# Cube.net
KiCad netlist of a schematic drawn in EAGLE
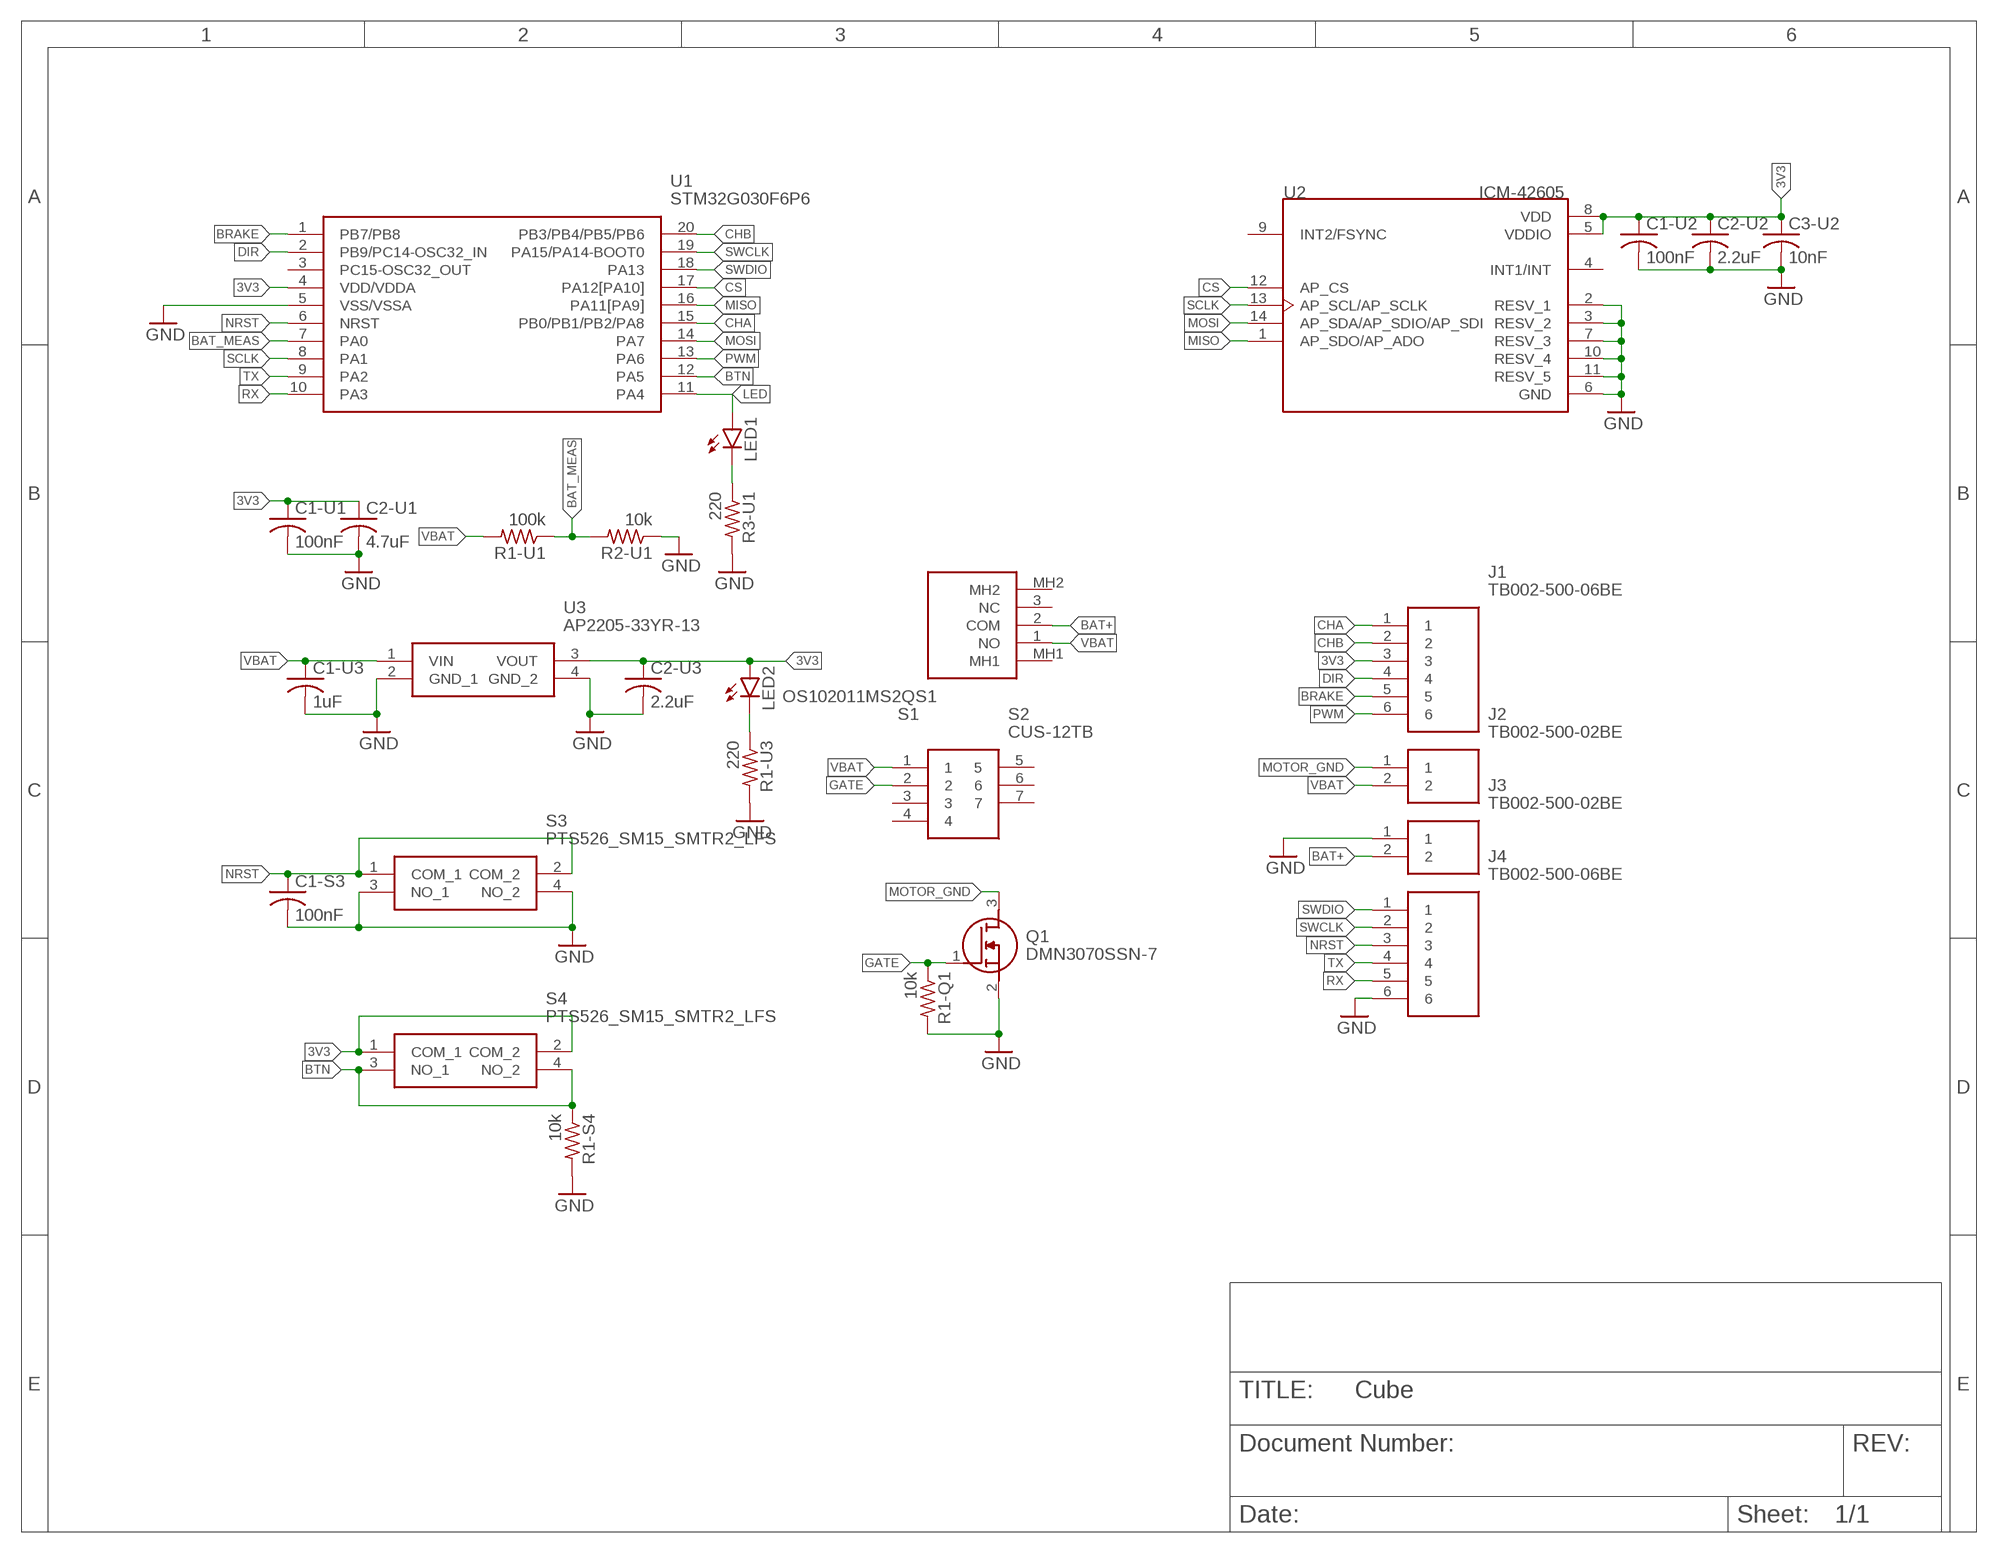
[diagram p0: schematic, sheet 1]

(export (version "E")
  (design (tool "Eeschema 10.0.6"))
  (components
    (comp (ref "C1-S3")
      (value "100nF")
      (footprint "eagle-import:C0805")
      (libsource (lib "eagle-import") (part "C-USC0805"))
    )
    (comp (ref "C1-U1")
      (value "100nF")
      (footprint "eagle-import:C0805")
      (libsource (lib "eagle-import") (part "C-USC0805"))
    )
    (comp (ref "C1-U2")
      (value "100nF")
      (footprint "eagle-import:C0805")
      (libsource (lib "eagle-import") (part "C-USC0805"))
    )
    (comp (ref "C1-U3")
      (value "1uF")
      (footprint "eagle-import:C0805")
      (libsource (lib "eagle-import") (part "C-USC0805"))
    )
    (comp (ref "C2-U1")
      (value "4.7uF")
      (footprint "eagle-import:C0805")
      (libsource (lib "eagle-import") (part "C-USC0805"))
    )
    (comp (ref "C2-U2")
      (value "2.2uF")
      (footprint "eagle-import:C0805")
      (libsource (lib "eagle-import") (part "C-USC0805"))
    )
    (comp (ref "C2-U3")
      (value "2.2uF")
      (footprint "eagle-import:C0805")
      (libsource (lib "eagle-import") (part "C-USC0805"))
    )
    (comp (ref "C3-U2")
      (value "10nF")
      (footprint "eagle-import:C0805")
      (libsource (lib "eagle-import") (part "C-USC0805"))
    )
    (comp (ref "J1")
      (value "TB002-500-06BE")
      (footprint "eagle-import:TB00250006BE")
      (fields (field (name "MOUSER_PART_NUMBER") "490-TB002-500-06BE"))
      (libsource (lib "eagle-import") (part "TB002-500-06BE"))
    )
    (comp (ref "J2")
      (value "TB002-500-02BE")
      (footprint "eagle-import:TB00250002BE")
      (fields (field (name "MOUSER_PART_NUMBER") "490-TB002-500-02BE"))
      (libsource (lib "eagle-import") (part "TB002-500-02BE"))
    )
    (comp (ref "J3")
      (value "TB002-500-02BE")
      (footprint "eagle-import:TB00250002BE")
      (fields (field (name "MOUSER_PART_NUMBER") "490-TB002-500-02BE"))
      (libsource (lib "eagle-import") (part "TB002-500-02BE"))
    )
    (comp (ref "J4")
      (value "TB002-500-06BE")
      (footprint "eagle-import:TB00250006BE")
      (fields (field (name "MOUSER_PART_NUMBER") "490-TB002-500-06BE"))
      (libsource (lib "eagle-import") (part "TB002-500-06BE"))
    )
    (comp (ref "LED1")
      (value "LEDCHIP-LED0805")
      (footprint "eagle-import:CHIP-LED0805")
      (libsource (lib "eagle-import") (part "LEDCHIP-LED0805"))
    )
    (comp (ref "LED2")
      (value "LEDCHIP-LED0805")
      (footprint "eagle-import:CHIP-LED0805")
      (libsource (lib "eagle-import") (part "LEDCHIP-LED0805"))
    )
    (comp (ref "Q1")
      (value "DMN3070SSN-7")
      (footprint "eagle-import:SOT95P285X140-3N")
      (fields (field (name "MOUSER_PART_NUMBER") "621-DMN3070SSN-7"))
      (libsource (lib "eagle-import") (part "DMN3070SSN-7"))
    )
    (comp (ref "R1-Q1")
      (value "10k")
      (footprint "eagle-import:R0805")
      (libsource (lib "eagle-import") (part "R-US_R0805"))
    )
    (comp (ref "R1-S4")
      (value "10k")
      (footprint "eagle-import:R0805")
      (libsource (lib "eagle-import") (part "R-US_R0805"))
    )
    (comp (ref "R1-U1")
      (value "100k")
      (footprint "eagle-import:R0805")
      (libsource (lib "eagle-import") (part "R-US_R0805"))
    )
    (comp (ref "R1-U3")
      (value "220")
      (footprint "eagle-import:R0805")
      (libsource (lib "eagle-import") (part "R-US_R0805"))
    )
    (comp (ref "R2-U1")
      (value "10k")
      (footprint "eagle-import:R0805")
      (libsource (lib "eagle-import") (part "R-US_R0805"))
    )
    (comp (ref "R3-U1")
      (value "220")
      (footprint "eagle-import:R0805")
      (libsource (lib "eagle-import") (part "R-US_R0805"))
    )
    (comp (ref "S1")
      (value "OS102011MS2QS1")
      (footprint "eagle-import:OS102011MS2QS1")
      (fields (field (name "MOUSER_PART_NUMBER") "611-OS102011MS2QS1"))
      (libsource (lib "eagle-import") (part "OS102011MS2QS1"))
    )
    (comp (ref "S2")
      (value "CUS-12TB")
      (footprint "eagle-import:CUS-12B")
      (libsource (lib "eagle-import") (part "CUS-12TB"))
    )
    (comp (ref "S3")
      (value "PTS526_SM15_SMTR2_LFS")
      (footprint "eagle-import:PTS526SM15SMTR2LFS")
      (fields
        (field (name "MANUFACTURER_PART_NUMBER") "PTS526 SM15 SMTR2 LFS")
        (field (name "MOUSER_PART_NUMBER") "611-PTS526SM15SMTR2L")
      )
      (libsource (lib "eagle-import") (part "PTS526_SM15_SMTR2_LFS"))
    )
    (comp (ref "S4")
      (value "PTS526_SM15_SMTR2_LFS")
      (footprint "eagle-import:PTS526SM15SMTR2LFS")
      (fields
        (field (name "MANUFACTURER_PART_NUMBER") "PTS526 SM15 SMTR2 LFS")
        (field (name "MOUSER_PART_NUMBER") "611-PTS526SM15SMTR2L")
      )
      (libsource (lib "eagle-import") (part "PTS526_SM15_SMTR2_LFS"))
    )
    (comp (ref "U1")
      (value "STM32G030F6P6")
      (footprint "eagle-import:SOP65P640X120-20N")
      (fields (field (name "MOUSER_PART_NUMBER") "511-STM32G030F6P6"))
      (libsource (lib "eagle-import") (part "STM32G030F6P6"))
    )
    (comp (ref "U2")
      (value "ICM-42605")
      (footprint "eagle-import:PQFN50P300X250X97-14N")
      (fields (field (name "MF") "TDK InvenSense"))
      (libsource (lib "eagle-import") (part "ICM-42605"))
    )
    (comp (ref "U3")
      (value "AP2205-33YR-13")
      (footprint "eagle-import:AP220533YR13")
      (fields (field (name "MOUSER_PART_NUMBER") "621-AP2205-33YR-13"))
      (libsource (lib "eagle-import") (part "AP2205-33YR-13"))
    )
  )
  (nets
    (net (code "1") (name "3V3") (class "Default")
      (node (ref "C1-U1") (pin "1") (pinfunction "1_1") (pintype "passive"))
      (node (ref "C1-U2") (pin "1") (pinfunction "1_1") (pintype "passive"))
      (node (ref "C2-U1") (pin "1") (pinfunction "1_1") (pintype "passive"))
      (node (ref "C2-U2") (pin "1") (pinfunction "1_1") (pintype "passive"))
      (node (ref "C2-U3") (pin "1") (pinfunction "1_1") (pintype "passive"))
      (node (ref "C3-U2") (pin "1") (pinfunction "1_1") (pintype "passive"))
      (node (ref "J1") (pin "3") (pinfunction "3_3") (pintype "bidirectional"))
      (node (ref "LED2") (pin "A") (pinfunction "A_A") (pintype "passive"))
      (node (ref "S4") (pin "1") (pinfunction "COM_1_1") (pintype "bidirectional"))
      (node (ref "S4") (pin "2") (pinfunction "COM_2_2") (pintype "bidirectional"))
      (node (ref "U1") (pin "4") (pinfunction "VDD/VDDA_4") (pintype "bidirectional"))
      (node (ref "U2") (pin "5") (pinfunction "VDDIO_5") (pintype "power_in"))
      (node (ref "U2") (pin "8") (pinfunction "VDD_8") (pintype "power_in"))
      (node (ref "U3") (pin "3") (pinfunction "VOUT_3") (pintype "bidirectional"))
    )
    (net (code "2") (name "BAT+") (class "Default")
      (node (ref "J3") (pin "2") (pinfunction "2_2") (pintype "bidirectional"))
      (node (ref "S1") (pin "2") (pinfunction "COM_2") (pintype "bidirectional"))
    )
    (net (code "3") (name "BAT_MEAS") (class "Default")
      (node (ref "R1-U1") (pin "1") (pinfunction "1_1") (pintype "passive"))
      (node (ref "R2-U1") (pin "2") (pinfunction "2_2") (pintype "passive"))
      (node (ref "U1") (pin "7") (pinfunction "PA0_7") (pintype "bidirectional"))
    )
    (net (code "4") (name "BRAKE") (class "Default")
      (node (ref "J1") (pin "5") (pinfunction "5_5") (pintype "bidirectional"))
      (node (ref "U1") (pin "1") (pinfunction "PB7/PB8_1") (pintype "bidirectional"))
    )
    (net (code "5") (name "BTN") (class "Default")
      (node (ref "R1-S4") (pin "1") (pinfunction "1_1") (pintype "passive"))
      (node (ref "S4") (pin "3") (pinfunction "NO_1_3") (pintype "bidirectional"))
      (node (ref "S4") (pin "4") (pinfunction "NO_2_4") (pintype "bidirectional"))
      (node (ref "U1") (pin "12") (pinfunction "PA5_12") (pintype "bidirectional"))
    )
    (net (code "6") (name "CHA") (class "Default")
      (node (ref "J1") (pin "1") (pinfunction "1_1") (pintype "bidirectional"))
      (node (ref "U1") (pin "15") (pinfunction "PB0/PB1/PB2/PA8_15") (pintype "bidirectional"))
    )
    (net (code "7") (name "CHB") (class "Default")
      (node (ref "J1") (pin "2") (pinfunction "2_2") (pintype "bidirectional"))
      (node (ref "U1") (pin "20") (pinfunction "PB3/PB4/PB5/PB6_20") (pintype "bidirectional"))
    )
    (net (code "8") (name "CS") (class "Default")
      (node (ref "U1") (pin "17") (pinfunction "PA12[PA10]_17") (pintype "bidirectional"))
      (node (ref "U2") (pin "12") (pinfunction "AP_CS_12") (pintype "input"))
    )
    (net (code "9") (name "DIR") (class "Default")
      (node (ref "J1") (pin "4") (pinfunction "4_4") (pintype "bidirectional"))
      (node (ref "U1") (pin "2") (pinfunction "PB9/PC14-OSC32_IN_2") (pintype "bidirectional"))
    )
    (net (code "10") (name "GATE") (class "Default")
      (node (ref "Q1") (pin "1") (pinfunction "G_1") (pintype "bidirectional"))
      (node (ref "R1-Q1") (pin "1") (pinfunction "1_1") (pintype "passive"))
      (node (ref "S2") (pin "2") (pinfunction "2_2") (pintype "bidirectional"))
    )
    (net (code "11") (name "GND") (class "Default")
      (node (ref "C1-S3") (pin "2") (pinfunction "2_2") (pintype "passive"))
      (node (ref "C1-U1") (pin "2") (pinfunction "2_2") (pintype "passive"))
      (node (ref "C1-U2") (pin "2") (pinfunction "2_2") (pintype "passive"))
      (node (ref "C1-U3") (pin "2") (pinfunction "2_2") (pintype "passive"))
      (node (ref "C2-U1") (pin "2") (pinfunction "2_2") (pintype "passive"))
      (node (ref "C2-U2") (pin "2") (pinfunction "2_2") (pintype "passive"))
      (node (ref "C2-U3") (pin "2") (pinfunction "2_2") (pintype "passive"))
      (node (ref "C3-U2") (pin "2") (pinfunction "2_2") (pintype "passive"))
      (node (ref "J3") (pin "1") (pinfunction "1_1") (pintype "bidirectional"))
      (node (ref "J4") (pin "6") (pinfunction "6_6") (pintype "bidirectional"))
      (node (ref "Q1") (pin "2") (pinfunction "S_2") (pintype "bidirectional"))
      (node (ref "R1-Q1") (pin "2") (pinfunction "2_2") (pintype "passive"))
      (node (ref "R1-S4") (pin "2") (pinfunction "2_2") (pintype "passive"))
      (node (ref "R1-U3") (pin "2") (pinfunction "2_2") (pintype "passive"))
      (node (ref "R2-U1") (pin "1") (pinfunction "1_1") (pintype "passive"))
      (node (ref "R3-U1") (pin "2") (pinfunction "2_2") (pintype "passive"))
      (node (ref "S3") (pin "3") (pinfunction "NO_1_3") (pintype "bidirectional"))
      (node (ref "S3") (pin "4") (pinfunction "NO_2_4") (pintype "bidirectional"))
      (node (ref "U1") (pin "5") (pinfunction "VSS/VSSA_5") (pintype "bidirectional"))
      (node (ref "U2") (pin "10") (pinfunction "RESV_4_10") (pintype "bidirectional"))
      (node (ref "U2") (pin "11") (pinfunction "RESV_5_11") (pintype "bidirectional"))
      (node (ref "U2") (pin "2") (pinfunction "RESV_1_2") (pintype "bidirectional"))
      (node (ref "U2") (pin "3") (pinfunction "RESV_2_3") (pintype "bidirectional"))
      (node (ref "U2") (pin "6") (pinfunction "GND_6") (pintype "power_in"))
      (node (ref "U2") (pin "7") (pinfunction "RESV_3_7") (pintype "bidirectional"))
      (node (ref "U3") (pin "2") (pinfunction "GND_1_2") (pintype "bidirectional"))
      (node (ref "U3") (pin "4") (pinfunction "GND_2_4") (pintype "bidirectional"))
    )
    (net (code "12") (name "LED") (class "Default")
      (node (ref "LED1") (pin "A") (pinfunction "A_A") (pintype "passive"))
      (node (ref "U1") (pin "11") (pinfunction "PA4_11") (pintype "bidirectional"))
    )
    (net (code "13") (name "MISO") (class "Default")
      (node (ref "U1") (pin "16") (pinfunction "PA11[PA9]_16") (pintype "bidirectional"))
      (node (ref "U2") (pin "1") (pinfunction "AP_SDO/AP_ADO_1") (pintype "output"))
    )
    (net (code "14") (name "MOSI") (class "Default")
      (node (ref "U1") (pin "14") (pinfunction "PA7_14") (pintype "bidirectional"))
      (node (ref "U2") (pin "14") (pinfunction "AP_SDA/AP_SDIO/AP_SDI_14") (pintype "bidirectional"))
    )
    (net (code "15") (name "MOTOR_GND") (class "Default")
      (node (ref "J2") (pin "1") (pinfunction "1_1") (pintype "bidirectional"))
      (node (ref "Q1") (pin "3") (pinfunction "D_3") (pintype "bidirectional"))
    )
    (net (code "16") (name "NRST") (class "Default")
      (node (ref "C1-S3") (pin "1") (pinfunction "1_1") (pintype "passive"))
      (node (ref "J4") (pin "3") (pinfunction "3_3") (pintype "bidirectional"))
      (node (ref "S3") (pin "1") (pinfunction "COM_1_1") (pintype "bidirectional"))
      (node (ref "S3") (pin "2") (pinfunction "COM_2_2") (pintype "bidirectional"))
      (node (ref "U1") (pin "6") (pinfunction "NRST_6") (pintype "bidirectional"))
    )
    (net (code "17") (name "Net-(LED1-PadC)") (class "Default")
      (node (ref "LED1") (pin "C") (pinfunction "C_C") (pintype "passive"))
      (node (ref "R3-U1") (pin "1") (pinfunction "1_1") (pintype "passive"))
    )
    (net (code "18") (name "Net-(LED2-PadC)") (class "Default")
      (node (ref "LED2") (pin "C") (pinfunction "C_C") (pintype "passive"))
      (node (ref "R1-U3") (pin "1") (pinfunction "1_1") (pintype "passive"))
    )
    (net (code "19") (name "PWM") (class "Default")
      (node (ref "J1") (pin "6") (pinfunction "6_6") (pintype "bidirectional"))
      (node (ref "U1") (pin "13") (pinfunction "PA6_13") (pintype "bidirectional"))
    )
    (net (code "20") (name "RX") (class "Default")
      (node (ref "J4") (pin "5") (pinfunction "5_5") (pintype "bidirectional"))
      (node (ref "U1") (pin "10") (pinfunction "PA3_10") (pintype "bidirectional"))
    )
    (net (code "21") (name "SCLK") (class "Default")
      (node (ref "U1") (pin "8") (pinfunction "PA1_8") (pintype "bidirectional"))
      (node (ref "U2") (pin "13") (pinfunction "AP_SCL/AP_SCLK_13") (pintype "input"))
    )
    (net (code "22") (name "SWCLK") (class "Default")
      (node (ref "J4") (pin "2") (pinfunction "2_2") (pintype "bidirectional"))
      (node (ref "U1") (pin "19") (pinfunction "PA15/PA14-BOOT0_19") (pintype "bidirectional"))
    )
    (net (code "23") (name "SWDIO") (class "Default")
      (node (ref "J4") (pin "1") (pinfunction "1_1") (pintype "bidirectional"))
      (node (ref "U1") (pin "18") (pinfunction "PA13_18") (pintype "bidirectional"))
    )
    (net (code "24") (name "TX") (class "Default")
      (node (ref "J4") (pin "4") (pinfunction "4_4") (pintype "bidirectional"))
      (node (ref "U1") (pin "9") (pinfunction "PA2_9") (pintype "bidirectional"))
    )
    (net (code "25") (name "VBAT") (class "Default")
      (node (ref "C1-U3") (pin "1") (pinfunction "1_1") (pintype "passive"))
      (node (ref "J2") (pin "2") (pinfunction "2_2") (pintype "bidirectional"))
      (node (ref "R1-U1") (pin "2") (pinfunction "2_2") (pintype "passive"))
      (node (ref "S1") (pin "1") (pinfunction "NO_1") (pintype "bidirectional"))
      (node (ref "S2") (pin "1") (pinfunction "1_1") (pintype "bidirectional"))
      (node (ref "U3") (pin "1") (pinfunction "VIN_1") (pintype "bidirectional"))
    )
    (net (code "26") (name "unconnected-(S1-NC-Pad3)") (class "Default")
      (node (ref "S1") (pin "3") (pinfunction "NC_3") (pintype "no_connect"))
    )
    (net (code "27") (name "unconnected-(S1-PadMH1)") (class "Default")
      (node (ref "S1") (pin "MH1") (pinfunction "MH1_MH1") (pintype "bidirectional"))
    )
    (net (code "28") (name "unconnected-(S1-PadMH2)") (class "Default")
      (node (ref "S1") (pin "MH2") (pinfunction "MH2_MH2") (pintype "bidirectional"))
    )
    (net (code "29") (name "unconnected-(S2-Pad3)") (class "Default")
      (node (ref "S2") (pin "3") (pinfunction "3_3") (pintype "bidirectional"))
    )
    (net (code "30") (name "unconnected-(S2-Pad4)") (class "Default")
      (node (ref "S2") (pin "4") (pinfunction "4_4") (pintype "bidirectional"))
    )
    (net (code "31") (name "unconnected-(S2-Pad5)") (class "Default")
      (node (ref "S2") (pin "5") (pinfunction "5_5") (pintype "bidirectional"))
    )
    (net (code "32") (name "unconnected-(S2-Pad6)") (class "Default")
      (node (ref "S2") (pin "6") (pinfunction "6_6") (pintype "bidirectional"))
    )
    (net (code "33") (name "unconnected-(S2-Pad7)") (class "Default")
      (node (ref "S2") (pin "7") (pinfunction "7_7") (pintype "bidirectional"))
    )
    (net (code "34") (name "unconnected-(U1-PC15-OSC32_OUT-Pad3)") (class "Default")
      (node (ref "U1") (pin "3") (pinfunction "PC15-OSC32_OUT_3") (pintype "bidirectional"))
    )
    (net (code "35") (name "unconnected-(U2-INT1{slash}INT-Pad4)") (class "Default")
      (node (ref "U2") (pin "4") (pinfunction "INT1/INT_4") (pintype "output"))
    )
    (net (code "36") (name "unconnected-(U2-INT2{slash}FSYNC-Pad9)") (class "Default")
      (node (ref "U2") (pin "9") (pinfunction "INT2/FSYNC_9") (pintype "bidirectional"))
    )
  )
)
